# LCD.net
KiCad netlist of a schematic drawn in Altium Designer
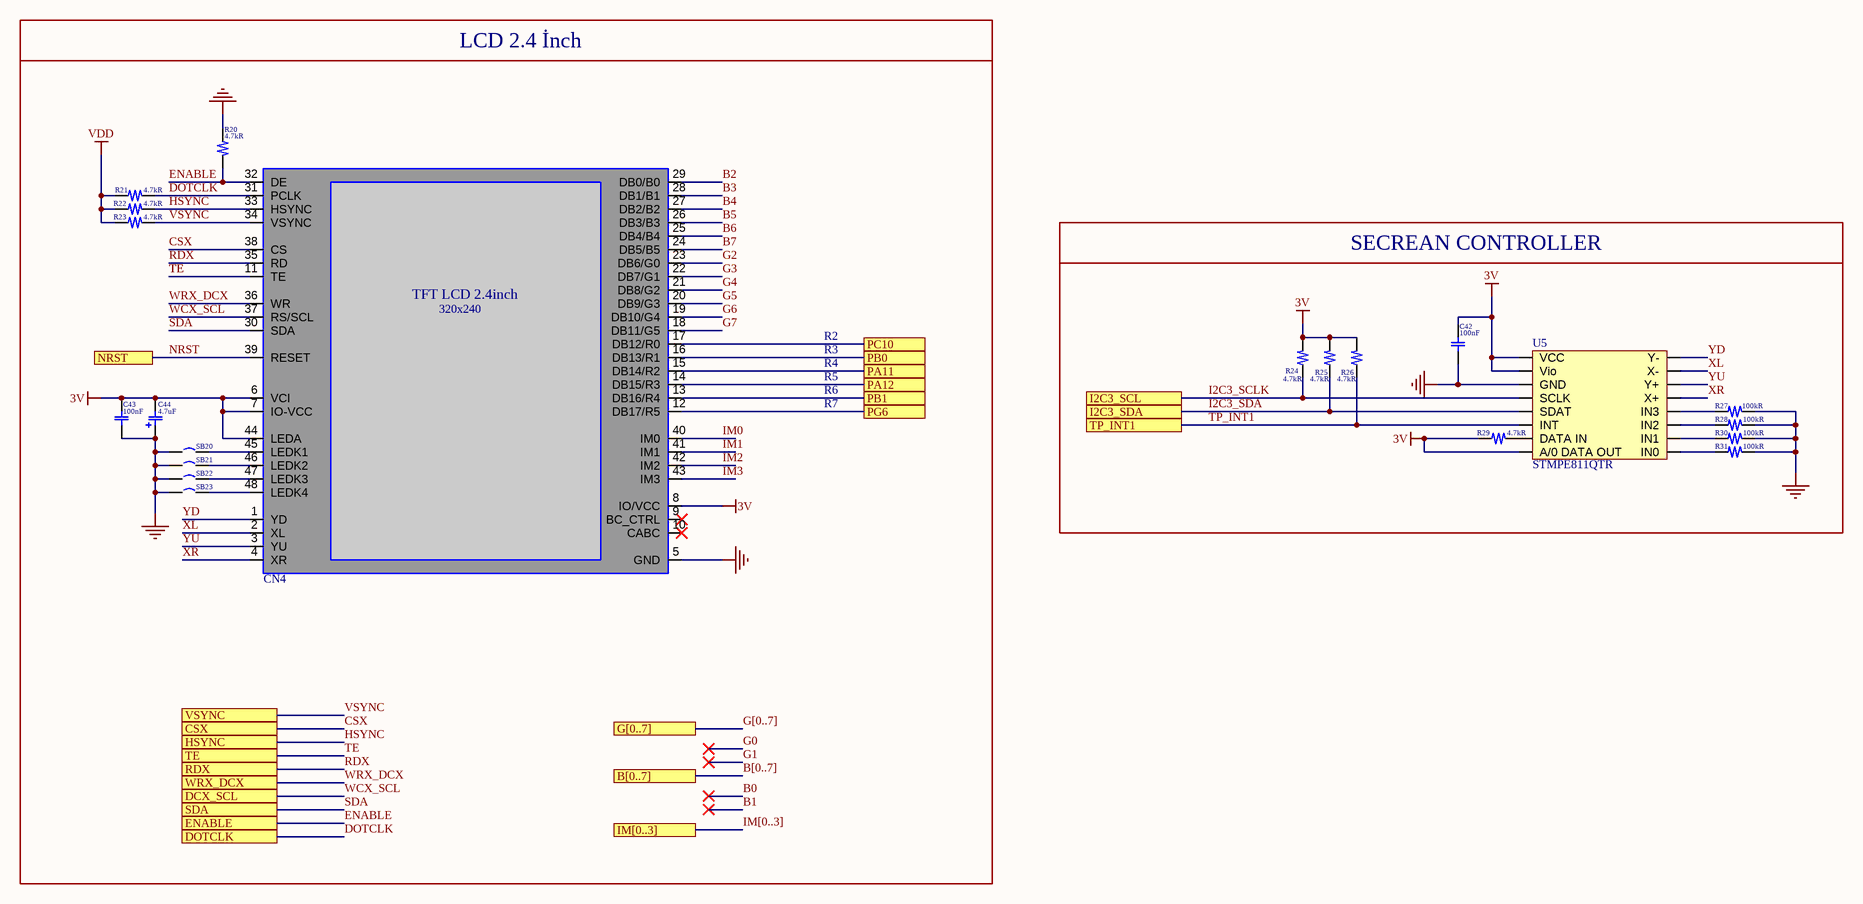
[diagram p0: LCD.SchDoc]

(export (version "E")
  (design (tool "Eeschema 10.0.6"))
  (components
    (comp (ref "C42")
      (value "100nF")
      (footprint "CAP-0402")
      (description "Multilayer Ceramic Capacitor, 0.1 uF, 25 V, ± 10%, X7R, 0402 [1005 Metric]")
      (fields
        (field (name "MANUFACTURER") "Yageo")
        (field (name "MANUFACTURER PART NUMBER") "CC0402KRX7R7BB104")
      )
      (libsource (lib "STM32") (part "CAP CER 100nF 16V X7R 0402"))
    )
    (comp (ref "C43")
      (value "100nF")
      (footprint "CAP-0402")
      (description "Multilayer Ceramic Capacitor, 0.1 uF, 25 V, ± 10%, X7R, 0402 [1005 Metric]")
      (fields
        (field (name "MANUFACTURER") "Yageo")
        (field (name "MANUFACTURER PART NUMBER") "CC0402KRX7R7BB104")
      )
      (libsource (lib "STM32") (part "CAP CER 100nF 16V X7R 0402"))
    )
    (comp (ref "C44")
      (value "4.7uF")
      (footprint "CAP-TANT")
      (description "Cap Tant Polymer 4.7uF 10V K CASE 20% (3.2 x 1.6 x 1mm) SMD 300m Ohm 105°C T/R")
      (fields
        (field (name "MANUFACTURER") "Kyocera AVX")
        (field (name "MANUFACTURER PART NUMBER") "TCJK475M010R0300E")
      )
      (libsource (lib "STM32") (part "C-TANT POLY 4.7UF 10V 1206"))
    )
    (comp (ref "CN4")
      (value "FRD240C48003-B")
      (footprint "LED 2.54 inch")
      (libsource (lib "STM32") (part "LCD 320X240 2.54ınc"))
    )
    (comp (ref "R20")
      (value "4.7kR")
      (footprint "RES-0402")
      (description "SMD Chip Resistor, 4.7 kOhm, ± 1%, 63 mW, 0402 [1005 Metric], Thick Film, General Purpose")
      (fields
        (field (name "MANUFACTURER") "Yageo")
        (field (name "MANUFACTURER PART NUMBER") "RC0402FR-074K7L")
      )
      (libsource (lib "STM32") (part "RES 4.7K OHM 1% 1/16W 0402"))
    )
    (comp (ref "R21")
      (value "4.7kR")
      (footprint "RES-0402")
      (description "SMD Chip Resistor, 4.7 kOhm, ± 1%, 63 mW, 0402 [1005 Metric], Thick Film, General Purpose")
      (fields
        (field (name "MANUFACTURER") "Yageo")
        (field (name "MANUFACTURER PART NUMBER") "RC0402FR-074K7L")
      )
      (libsource (lib "STM32") (part "RES 4.7K OHM 1% 1/16W 0402"))
    )
    (comp (ref "R22")
      (value "4.7kR")
      (footprint "RES-0402")
      (description "SMD Chip Resistor, 4.7 kOhm, ± 1%, 63 mW, 0402 [1005 Metric], Thick Film, General Purpose")
      (fields
        (field (name "MANUFACTURER") "Yageo")
        (field (name "MANUFACTURER PART NUMBER") "RC0402FR-074K7L")
      )
      (libsource (lib "STM32") (part "RES 4.7K OHM 1% 1/16W 0402"))
    )
    (comp (ref "R23")
      (value "4.7kR")
      (footprint "RES-0402")
      (description "SMD Chip Resistor, 4.7 kOhm, ± 1%, 63 mW, 0402 [1005 Metric], Thick Film, General Purpose")
      (fields
        (field (name "MANUFACTURER") "Yageo")
        (field (name "MANUFACTURER PART NUMBER") "RC0402FR-074K7L")
      )
      (libsource (lib "STM32") (part "RES 4.7K OHM 1% 1/16W 0402"))
    )
    (comp (ref "R24")
      (value "4.7kR")
      (footprint "RES-0402")
      (description "SMD Chip Resistor, 4.7 kOhm, ± 1%, 63 mW, 0402 [1005 Metric], Thick Film, General Purpose")
      (fields
        (field (name "MANUFACTURER") "Yageo")
        (field (name "MANUFACTURER PART NUMBER") "RC0402FR-074K7L")
      )
      (libsource (lib "STM32") (part "RES 4.7K OHM 1% 1/16W 0402"))
    )
    (comp (ref "R25")
      (value "4.7kR")
      (footprint "RES-0402")
      (description "SMD Chip Resistor, 4.7 kOhm, ± 1%, 63 mW, 0402 [1005 Metric], Thick Film, General Purpose")
      (fields
        (field (name "MANUFACTURER") "Yageo")
        (field (name "MANUFACTURER PART NUMBER") "RC0402FR-074K7L")
      )
      (libsource (lib "STM32") (part "RES 4.7K OHM 1% 1/16W 0402"))
    )
    (comp (ref "R26")
      (value "4.7kR")
      (footprint "RES-0402")
      (description "SMD Chip Resistor, 4.7 kOhm, ± 1%, 63 mW, 0402 [1005 Metric], Thick Film, General Purpose")
      (fields
        (field (name "MANUFACTURER") "Yageo")
        (field (name "MANUFACTURER PART NUMBER") "RC0402FR-074K7L")
      )
      (libsource (lib "STM32") (part "RES 4.7K OHM 1% 1/16W 0402"))
    )
    (comp (ref "R27")
      (value "100kR")
      (footprint "RES-0402")
      (description "SMD Chip Resistor, 100 kOhm, ± 1%, 63 mW, 0402 [1005 Metric], Thick Film, General Purpose")
      (fields
        (field (name "MANUFACTURER") "Yageo")
        (field (name "MANUFACTURER PART NUMBER") "RC0402FR-07100KL")
      )
      (libsource (lib "STM32") (part "RES 100K OHM 1% 1/16W 0402"))
    )
    (comp (ref "R28")
      (value "100kR")
      (footprint "RES-0402")
      (description "SMD Chip Resistor, 100 kOhm, ± 1%, 63 mW, 0402 [1005 Metric], Thick Film, General Purpose")
      (fields
        (field (name "MANUFACTURER") "Yageo")
        (field (name "MANUFACTURER PART NUMBER") "RC0402FR-07100KL")
      )
      (libsource (lib "STM32") (part "RES 100K OHM 1% 1/16W 0402"))
    )
    (comp (ref "R29")
      (value "4.7kR")
      (footprint "RES-0402")
      (description "SMD Chip Resistor, 4.7 kOhm, ± 1%, 63 mW, 0402 [1005 Metric], Thick Film, General Purpose")
      (fields
        (field (name "MANUFACTURER") "Yageo")
        (field (name "MANUFACTURER PART NUMBER") "RC0402FR-074K7L")
      )
      (libsource (lib "STM32") (part "RES 4.7K OHM 1% 1/16W 0402"))
    )
    (comp (ref "R30")
      (value "100kR")
      (footprint "RES-0402")
      (description "SMD Chip Resistor, 100 kOhm, ± 1%, 63 mW, 0402 [1005 Metric], Thick Film, General Purpose")
      (fields
        (field (name "MANUFACTURER") "Yageo")
        (field (name "MANUFACTURER PART NUMBER") "RC0402FR-07100KL")
      )
      (libsource (lib "STM32") (part "RES 100K OHM 1% 1/16W 0402"))
    )
    (comp (ref "R31")
      (value "100kR")
      (footprint "RES-0402")
      (description "SMD Chip Resistor, 100 kOhm, ± 1%, 63 mW, 0402 [1005 Metric], Thick Film, General Purpose")
      (fields
        (field (name "MANUFACTURER") "Yageo")
        (field (name "MANUFACTURER PART NUMBER") "RC0402FR-07100KL")
      )
      (libsource (lib "STM32") (part "RES 100K OHM 1% 1/16W 0402"))
    )
    (comp (ref "SB20")
      (value "RC0402JR-070RL")
      (footprint "RES-0402")
      (description "Zero Ohm Resistor, Jumper, 0402 [1005 Metric], Thick Film, 62.5 mW, 1 A, Surface Mount")
      (fields
        (field (name "MANUFACTURER") "Yageo")
        (field (name "MANUFACTURER PART NUMBER") "RC0603JR-070RL")
      )
      (libsource (lib "STM32") (part "RES 0 OHM JUMPER 1/10W 0603"))
    )
    (comp (ref "SB21")
      (value "RC0402JR-070RL")
      (footprint "RES-0402")
      (description "Zero Ohm Resistor, Jumper, 0402 [1005 Metric], Thick Film, 62.5 mW, 1 A, Surface Mount")
      (fields
        (field (name "MANUFACTURER") "Yageo")
        (field (name "MANUFACTURER PART NUMBER") "RC0603JR-070RL")
      )
      (libsource (lib "STM32") (part "RES 0 OHM JUMPER 1/10W 0603"))
    )
    (comp (ref "SB22")
      (value "RC0402JR-070RL")
      (footprint "RES-0402")
      (description "Zero Ohm Resistor, Jumper, 0402 [1005 Metric], Thick Film, 62.5 mW, 1 A, Surface Mount")
      (fields
        (field (name "MANUFACTURER") "Yageo")
        (field (name "MANUFACTURER PART NUMBER") "RC0603JR-070RL")
      )
      (libsource (lib "STM32") (part "RES 0 OHM JUMPER 1/10W 0603"))
    )
    (comp (ref "SB23")
      (value "RC0402JR-070RL")
      (footprint "RES-0402")
      (description "Zero Ohm Resistor, Jumper, 0402 [1005 Metric], Thick Film, 62.5 mW, 1 A, Surface Mount")
      (fields
        (field (name "MANUFACTURER") "Yageo")
        (field (name "MANUFACTURER PART NUMBER") "RC0603JR-070RL")
      )
      (libsource (lib "STM32") (part "RES 0 OHM JUMPER 1/10W 0603"))
    )
    (comp (ref "U5")
      (value "STMPE811QTR")
      (footprint "QFN16")
      (description "S-Touch® advanced resistive touchscreen controller with 8-bit GPIO expander")
      (fields (field (name "MANUFACTURER") "STMicroelectronics"))
      (libsource (lib "STM32") (part "IC SCREEN CNTRL 12BIT 16QFN"))
    )
  )
  (nets
    (net (code "3") (name "/B2") (class "Default")
      (node (ref "CN4") (pin "29") (pinfunction "DB0/B0_29") (pintype "passive"))
    )
    (net (code "4") (name "/B3") (class "Default")
      (node (ref "CN4") (pin "28") (pinfunction "DB1/B1_28") (pintype "passive"))
    )
    (net (code "5") (name "/B4") (class "Default")
      (node (ref "CN4") (pin "27") (pinfunction "DB2/B2_27") (pintype "passive"))
    )
    (net (code "6") (name "/B5") (class "Default")
      (node (ref "CN4") (pin "26") (pinfunction "DB3/B3_26") (pintype "passive"))
    )
    (net (code "7") (name "/B6") (class "Default")
      (node (ref "CN4") (pin "25") (pinfunction "DB4/B4_25") (pintype "passive"))
    )
    (net (code "8") (name "/B7") (class "Default")
      (node (ref "CN4") (pin "24") (pinfunction "DB5/B5_24") (pintype "passive"))
    )
    (net (code "10") (name "/CSX") (class "Default")
      (node (ref "CN4") (pin "38") (pinfunction "CS_38") (pintype "passive"))
    )
    (net (code "11") (name "/DOTCLK") (class "Default")
      (node (ref "CN4") (pin "31") (pinfunction "PCLK_31") (pintype "passive"))
      (node (ref "R21") (pin "2") (pinfunction "2_2") (pintype "passive"))
    )
    (net (code "12") (name "/ENABLE") (class "Default")
      (node (ref "CN4") (pin "32") (pinfunction "DE_32") (pintype "passive"))
      (node (ref "R20") (pin "2") (pinfunction "2_2") (pintype "passive"))
    )
    (net (code "15") (name "/G2") (class "Default")
      (node (ref "CN4") (pin "23") (pinfunction "DB6/G0_23") (pintype "passive"))
    )
    (net (code "16") (name "/G3") (class "Default")
      (node (ref "CN4") (pin "22") (pinfunction "DB7/G1_22") (pintype "passive"))
    )
    (net (code "17") (name "/G4") (class "Default")
      (node (ref "CN4") (pin "21") (pinfunction "DB8/G2_21") (pintype "passive"))
    )
    (net (code "18") (name "/G5") (class "Default")
      (node (ref "CN4") (pin "20") (pinfunction "DB9/G3_20") (pintype "passive"))
    )
    (net (code "19") (name "/G6") (class "Default")
      (node (ref "CN4") (pin "19") (pinfunction "DB10/G4_19") (pintype "passive"))
    )
    (net (code "20") (name "/G7") (class "Default")
      (node (ref "CN4") (pin "18") (pinfunction "DB11/G5_18") (pintype "passive"))
    )
    (net (code "22") (name "/HSYNC") (class "Default")
      (node (ref "CN4") (pin "33") (pinfunction "HSYNC_33") (pintype "passive"))
      (node (ref "R22") (pin "2") (pinfunction "2_2") (pintype "passive"))
    )
    (net (code "23") (name "/I2C3_SCLK") (class "Default")
      (node (ref "R24") (pin "1") (pinfunction "1_1") (pintype "passive"))
      (node (ref "U5") (pin "4") (pinfunction "SCLK_4") (pintype "passive"))
    )
    (net (code "24") (name "/I2C3_SDA") (class "Default")
      (node (ref "R25") (pin "1") (pinfunction "1_1") (pintype "passive"))
      (node (ref "U5") (pin "5") (pinfunction "SDAT_5") (pintype "passive"))
    )
    (net (code "25") (name "/IM0") (class "Default")
      (node (ref "CN4") (pin "40") (pinfunction "IM0_40") (pintype "passive"))
    )
    (net (code "26") (name "/IM1") (class "Default")
      (node (ref "CN4") (pin "41") (pinfunction "IM1_41") (pintype "passive"))
    )
    (net (code "27") (name "/IM2") (class "Default")
      (node (ref "CN4") (pin "42") (pinfunction "IM2_42") (pintype "passive"))
    )
    (net (code "28") (name "/IM3") (class "Default")
      (node (ref "CN4") (pin "43") (pinfunction "IM3_43") (pintype "passive"))
    )
    (net (code "30") (name "/NRST") (class "Default")
      (node (ref "CN4") (pin "39") (pinfunction "RESET_39") (pintype "passive"))
    )
    (net (code "31") (name "/PA11") (class "Default")
      (node (ref "CN4") (pin "15") (pinfunction "DB14/R2_15") (pintype "passive"))
    )
    (net (code "32") (name "/PA12") (class "Default")
      (node (ref "CN4") (pin "14") (pinfunction "DB15/R3_14") (pintype "passive"))
    )
    (net (code "33") (name "/PB0") (class "Default")
      (node (ref "CN4") (pin "16") (pinfunction "DB13/R1_16") (pintype "passive"))
    )
    (net (code "34") (name "/PB1") (class "Default")
      (node (ref "CN4") (pin "13") (pinfunction "DB16/R4_13") (pintype "passive"))
    )
    (net (code "35") (name "/PC10") (class "Default")
      (node (ref "CN4") (pin "17") (pinfunction "DB12/R0_17") (pintype "passive"))
    )
    (net (code "36") (name "/PG6") (class "Default")
      (node (ref "CN4") (pin "12") (pinfunction "DB17/R5_12") (pintype "passive"))
    )
    (net (code "37") (name "/RDX") (class "Default")
      (node (ref "CN4") (pin "35") (pinfunction "RD_35") (pintype "passive"))
    )
    (net (code "38") (name "/SDA") (class "Default")
      (node (ref "CN4") (pin "30") (pinfunction "SDA_30") (pintype "passive"))
    )
    (net (code "39") (name "/TE") (class "Default")
      (node (ref "CN4") (pin "11") (pinfunction "TE_11") (pintype "passive"))
    )
    (net (code "40") (name "/TP_INT1") (class "Default")
      (node (ref "R26") (pin "1") (pinfunction "1_1") (pintype "passive"))
      (node (ref "U5") (pin "2") (pinfunction "INT_2") (pintype "passive"))
    )
    (net (code "41") (name "/VSYNC") (class "Default")
      (node (ref "CN4") (pin "34") (pinfunction "VSYNC_34") (pintype "passive"))
      (node (ref "R23") (pin "2") (pinfunction "2_2") (pintype "passive"))
    )
    (net (code "42") (name "/WCX_SCL") (class "Default")
      (node (ref "CN4") (pin "37") (pinfunction "RS/SCL_37") (pintype "passive"))
    )
    (net (code "43") (name "/WRX_DCX") (class "Default")
      (node (ref "CN4") (pin "36") (pinfunction "WR_36") (pintype "passive"))
    )
    (net (code "44") (name "/XL") (class "Default")
      (node (ref "CN4") (pin "2") (pinfunction "XL_2") (pintype "passive"))
      (node (ref "U5") (pin "16") (pinfunction "X-_16") (pintype "passive"))
    )
    (net (code "45") (name "/XR") (class "Default")
      (node (ref "CN4") (pin "4") (pinfunction "XR_4") (pintype "passive"))
      (node (ref "U5") (pin "13") (pinfunction "X+_13") (pintype "passive"))
    )
    (net (code "46") (name "/YD") (class "Default")
      (node (ref "CN4") (pin "1") (pinfunction "YD_1") (pintype "passive"))
      (node (ref "U5") (pin "1") (pinfunction "Y-_1") (pintype "passive"))
    )
    (net (code "47") (name "/YU") (class "Default")
      (node (ref "CN4") (pin "3") (pinfunction "YU_3") (pintype "passive"))
      (node (ref "U5") (pin "15") (pinfunction "Y+_15") (pintype "passive"))
    )
    (net (code "48") (name "3V") (class "Default")
      (node (ref "C42") (pin "2") (pinfunction "2_2") (pintype "passive"))
      (node (ref "C43") (pin "2") (pinfunction "2_2") (pintype "passive"))
      (node (ref "C44") (pin "2") (pinfunction "2_2") (pintype "passive"))
      (node (ref "CN4") (pin "44") (pinfunction "LEDA_44") (pintype "passive"))
      (node (ref "CN4") (pin "6") (pinfunction "VCI_6") (pintype "passive"))
      (node (ref "CN4") (pin "7") (pinfunction "IO-VCC_7") (pintype "passive"))
      (node (ref "CN4") (pin "8") (pinfunction "IO/VCC_8") (pintype "passive"))
      (node (ref "R24") (pin "2") (pinfunction "2_2") (pintype "passive"))
      (node (ref "R25") (pin "2") (pinfunction "2_2") (pintype "passive"))
      (node (ref "R26") (pin "2") (pinfunction "2_2") (pintype "passive"))
      (node (ref "R29") (pin "1") (pinfunction "1_1") (pintype "passive"))
      (node (ref "U5") (pin "14") (pinfunction "Vio_14") (pintype "passive"))
      (node (ref "U5") (pin "3") (pinfunction "A/0_DATA_OUT_3") (pintype "passive"))
      (node (ref "U5") (pin "6") (pinfunction "VCC_6") (pintype "passive"))
    )
    (net (code "49") (name "GND") (class "Default")
      (node (ref "C42") (pin "1") (pinfunction "1_1") (pintype "passive"))
      (node (ref "C43") (pin "1") (pinfunction "1_1") (pintype "passive"))
      (node (ref "C44") (pin "1") (pinfunction "1_1") (pintype "passive"))
      (node (ref "CN4") (pin "5") (pinfunction "GND_5") (pintype "passive"))
      (node (ref "R20") (pin "1") (pinfunction "1_1") (pintype "passive"))
      (node (ref "R27") (pin "2") (pinfunction "2_2") (pintype "passive"))
      (node (ref "R28") (pin "2") (pinfunction "2_2") (pintype "passive"))
      (node (ref "R30") (pin "2") (pinfunction "2_2") (pintype "passive"))
      (node (ref "R31") (pin "2") (pinfunction "2_2") (pintype "passive"))
      (node (ref "SB20") (pin "1") (pinfunction "1_1") (pintype "passive"))
      (node (ref "SB21") (pin "1") (pinfunction "1_1") (pintype "passive"))
      (node (ref "SB22") (pin "1") (pinfunction "1_1") (pintype "passive"))
      (node (ref "SB23") (pin "1") (pinfunction "1_1") (pintype "passive"))
      (node (ref "U5") (pin "10") (pinfunction "GND_10") (pintype "passive"))
    )
    (net (code "50") (name "Net-(CN4-LEDK1)") (class "Default")
      (node (ref "CN4") (pin "45") (pinfunction "LEDK1_45") (pintype "passive"))
      (node (ref "SB20") (pin "2") (pinfunction "2_2") (pintype "passive"))
    )
    (net (code "51") (name "Net-(CN4-LEDK2)") (class "Default")
      (node (ref "CN4") (pin "46") (pinfunction "LEDK2_46") (pintype "passive"))
      (node (ref "SB21") (pin "2") (pinfunction "2_2") (pintype "passive"))
    )
    (net (code "52") (name "Net-(CN4-LEDK3)") (class "Default")
      (node (ref "CN4") (pin "47") (pinfunction "LEDK3_47") (pintype "passive"))
      (node (ref "SB22") (pin "2") (pinfunction "2_2") (pintype "passive"))
    )
    (net (code "53") (name "Net-(CN4-LEDK4)") (class "Default")
      (node (ref "CN4") (pin "48") (pinfunction "LEDK4_48") (pintype "passive"))
      (node (ref "SB23") (pin "2") (pinfunction "2_2") (pintype "passive"))
    )
    (net (code "54") (name "Net-(U5-DATA_IN)") (class "Default")
      (node (ref "R29") (pin "2") (pinfunction "2_2") (pintype "passive"))
      (node (ref "U5") (pin "7") (pinfunction "DATA_IN_7") (pintype "passive"))
    )
    (net (code "55") (name "Net-(U5-IN0)") (class "Default")
      (node (ref "R31") (pin "1") (pinfunction "1_1") (pintype "passive"))
      (node (ref "U5") (pin "8") (pinfunction "IN0_8") (pintype "passive"))
    )
    (net (code "56") (name "Net-(U5-IN1)") (class "Default")
      (node (ref "R30") (pin "1") (pinfunction "1_1") (pintype "passive"))
      (node (ref "U5") (pin "9") (pinfunction "IN1_9") (pintype "passive"))
    )
    (net (code "57") (name "Net-(U5-IN2)") (class "Default")
      (node (ref "R28") (pin "1") (pinfunction "1_1") (pintype "passive"))
      (node (ref "U5") (pin "11") (pinfunction "IN2_11") (pintype "passive"))
    )
    (net (code "58") (name "Net-(U5-IN3)") (class "Default")
      (node (ref "R27") (pin "1") (pinfunction "1_1") (pintype "passive"))
      (node (ref "U5") (pin "12") (pinfunction "IN3_12") (pintype "passive"))
    )
    (net (code "59") (name "VDD") (class "Default")
      (node (ref "R21") (pin "1") (pinfunction "1_1") (pintype "passive"))
      (node (ref "R22") (pin "1") (pinfunction "1_1") (pintype "passive"))
      (node (ref "R23") (pin "1") (pinfunction "1_1") (pintype "passive"))
    )
    (net (code "60") (name "unconnected-(CN4-BC_CTRL-Pad9)") (class "Default")
      (node (ref "CN4") (pin "9") (pinfunction "BC_CTRL_9") (pintype "passive+no_connect"))
    )
    (net (code "61") (name "unconnected-(CN4-CABC-Pad10)") (class "Default")
      (node (ref "CN4") (pin "10") (pinfunction "CABC_10") (pintype "passive+no_connect"))
    )
  )
)
